# BiasTee.net
KiCad netlist of a schematic drawn in Altium Designer
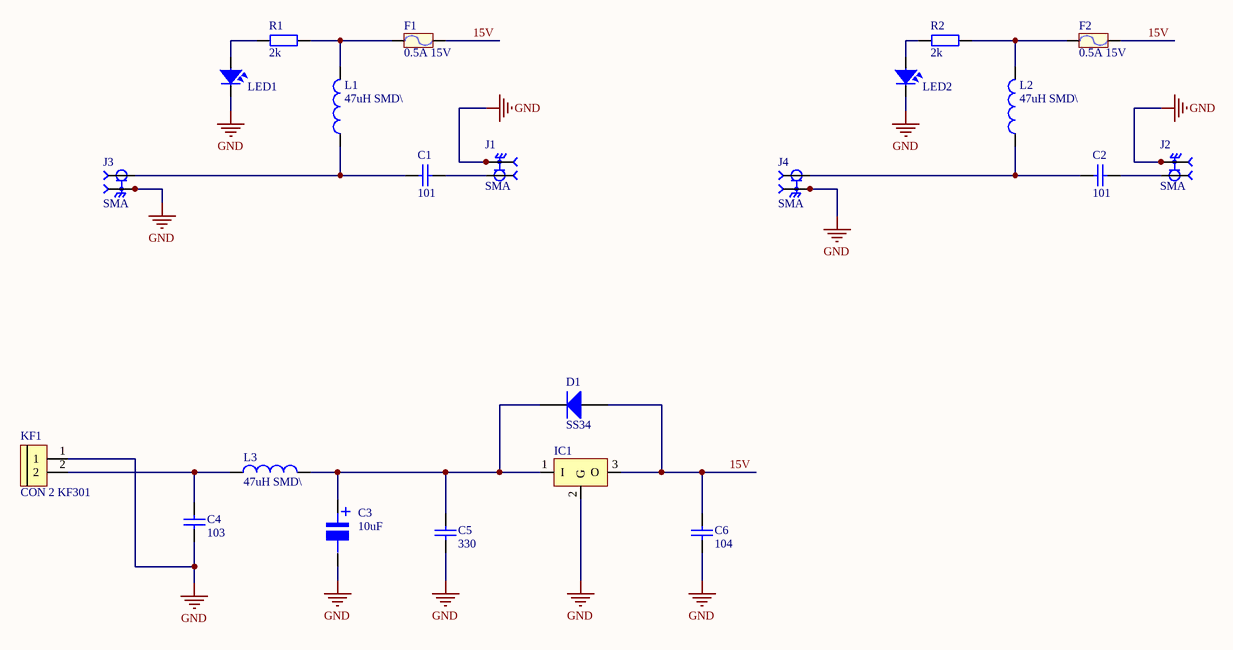
[diagram p0: BiasTee.SchDoc]

(export (version "E")
  (design (tool "Eeschema 10.0.6"))
  (components
    (comp (ref "C1")
      (value "101")
      (footprint "tu 0805")
      (description "Dán")
      (libsource (lib "Tu dien") (part "Tu 0805 101 50V 20%"))
    )
    (comp (ref "C2")
      (value "101")
      (footprint "tu 0805")
      (description "Dán")
      (libsource (lib "Tu dien") (part "Tu 0805 101 50V 20%"))
    )
    (comp (ref "C3")
      (value "10uF")
      (footprint "tu nhom 5 (c)")
      (description "Dán")
      (libsource (lib "Tu dien") (part "Tu Nhom 10uF 20V"))
    )
    (comp (ref "C4")
      (value "103")
      (footprint "tu 1206")
      (description "Dán")
      (libsource (lib "Tu dien") (part "Tu 1206 103 50V 10%"))
    )
    (comp (ref "C5")
      (value "330")
      (footprint "tu 1206")
      (description "Dán")
      (libsource (lib "Tu dien") (part "Tu 1206 103 50V 10%"))
    )
    (comp (ref "C6")
      (value "104")
      (footprint "tu 1206")
      (description "Dán")
      (libsource (lib "Tu dien") (part "Tu 1206 103 50V 10%"))
    )
    (comp (ref "D1")
      (value "SS34")
      (footprint "DIODE SMA")
      (description "Dán")
      (libsource (lib "Diode") (part "Diode SS34 ( 1N5822 )"))
    )
    (comp (ref "F1")
      (value "0.5A 15V")
      (footprint "Cau chi tu phuc hoi 2A 24V SMD1812")
      (description "2A 24V SMD1812")
      (libsource (lib "Component") (part "Cau chi tu phuc hoi 2A 24V SMD1812"))
    )
    (comp (ref "F2")
      (value "0.5A 15V")
      (footprint "Cau chi tu phuc hoi 2A 24V SMD1812")
      (description "2A 24V SMD1812")
      (libsource (lib "Component") (part "Cau chi tu phuc hoi 2A 24V SMD1812"))
    )
    (comp (ref "IC1")
      (value "LM78xx")
      (footprint "TO220H1")
      (description "Positive Voltage Regulator")
      (fields (field (name "PUBLISHER") "Altium Limited"))
      (libsource (lib "Library") (part "LM78xx"))
    )
    (comp (ref "J1")
      (value "SMA")
      (footprint "RFSOLUTIONS_CON-SMA-EDGE-S")
      (description "SMA Connector Jack, Female Socket - Board Edge, End Launch Solder")
      (fields (field (name "MF") "RF Solutions") (field (name "DIGI-KEY_PART_NUMBER") "CON-SMA-EDGE-S-ND"))
      (libsource (lib "CON-SMA-EDGE-S") (part "CON-SMA-EDGE-S"))
    )
    (comp (ref "J2")
      (value "SMA")
      (footprint "RFSOLUTIONS_CON-SMA-EDGE-S")
      (description "SMA Connector Jack, Female Socket - Board Edge, End Launch Solder")
      (fields (field (name "MF") "RF Solutions") (field (name "DIGI-KEY_PART_NUMBER") "CON-SMA-EDGE-S-ND"))
      (libsource (lib "CON-SMA-EDGE-S") (part "CON-SMA-EDGE-S"))
    )
    (comp (ref "J3")
      (value "SMA")
      (footprint "RFSOLUTIONS_CON-SMA-EDGE-S")
      (description "SMA Connector Jack, Female Socket - Board Edge, End Launch Solder")
      (fields (field (name "MF") "RF Solutions") (field (name "DIGI-KEY_PART_NUMBER") "CON-SMA-EDGE-S-ND"))
      (libsource (lib "CON-SMA-EDGE-S") (part "CON-SMA-EDGE-S"))
    )
    (comp (ref "J4")
      (value "SMA")
      (footprint "RFSOLUTIONS_CON-SMA-EDGE-S")
      (description "SMA Connector Jack, Female Socket - Board Edge, End Launch Solder")
      (fields (field (name "MF") "RF Solutions") (field (name "DIGI-KEY_PART_NUMBER") "CON-SMA-EDGE-S-ND"))
      (libsource (lib "CON-SMA-EDGE-S") (part "CON-SMA-EDGE-S"))
    )
    (comp (ref "KF1")
      (value "CON 2 KF301")
      (footprint "Con 2 KF301 5.08")
      (description "Cắm")
      (libsource (lib "Connector") (part "CON 2 KF301"))
    )
    (comp (ref "L1")
      (value "47uH SM~{D}")
      (footprint "IND_1210")
      (description "Fixed Inductors 18uH 10% 2.52MHz")
      (fields
        (field (name "MANUFACTURER") "Wurth Electronics")
        (field (name "MANUFACTURER PART NUMBER") "CMH322522-180KL")
      )
      (libsource (lib "Cuon Cam") (part "IND_18uH-0.12A-10%-SMD"))
    )
    (comp (ref "L2")
      (value "47uH SM~{D}")
      (footprint "IND_1210")
      (description "Fixed Inductors 18uH 10% 2.52MHz")
      (fields
        (field (name "MANUFACTURER") "Wurth Electronics")
        (field (name "MANUFACTURER PART NUMBER") "CMH322522-180KL")
      )
      (libsource (lib "Cuon Cam") (part "IND_18uH-0.12A-10%-SMD"))
    )
    (comp (ref "L3")
      (value "47uH SM~{D}")
      (footprint "IND_1210")
      (description "Fixed Inductors 18uH 10% 2.52MHz")
      (fields
        (field (name "MANUFACTURER") "Wurth Electronics")
        (field (name "MANUFACTURER PART NUMBER") "CMH322522-180KL")
      )
      (libsource (lib "Cuon Cam") (part "IND_18uH-0.12A-10%-SMD"))
    )
    (comp (ref "LED1")
      (value "LED")
      (footprint "LED-1206-Green")
      (libsource (lib "Library") (part "LED SMD"))
    )
    (comp (ref "LED2")
      (value "LED")
      (footprint "LED-1206-Green")
      (libsource (lib "Library") (part "LED SMD"))
    )
    (comp (ref "R1")
      (value "2k")
      (footprint "tro smd 0805")
      (description "Dán")
      (libsource (lib "Dien Tro") (part "Tro 0805 1% 2k"))
    )
    (comp (ref "R2")
      (value "2k")
      (footprint "tro smd 0805")
      (description "Dán")
      (libsource (lib "Dien Tro") (part "Tro 0805 1% 2k"))
    )
  )
  (nets
    (net (code "1") (name "/15V") (class "Default")
      (node (ref "C6") (pin "1") (pinfunction "1_1") (pintype "passive"))
      (node (ref "D1") (pin "1") (pinfunction "A_1") (pintype "passive"))
      (node (ref "F1") (pin "2") (pinfunction "2_2") (pintype "passive"))
      (node (ref "F2") (pin "2") (pinfunction "2_2") (pintype "passive"))
      (node (ref "IC1") (pin "3") (pinfunction "O_3") (pintype "power_in"))
    )
    (net (code "2") (name "GND") (class "Default")
      (node (ref "C3") (pin "2") (pinfunction "2_2") (pintype "passive"))
      (node (ref "C4") (pin "2") (pinfunction "2_2") (pintype "passive"))
      (node (ref "C5") (pin "2") (pinfunction "2_2") (pintype "passive"))
      (node (ref "C6") (pin "2") (pinfunction "2_2") (pintype "passive"))
      (node (ref "IC1") (pin "2") (pinfunction "G_2") (pintype "power_in"))
      (node (ref "J1") (pin "G1") (pinfunction "2_G1") (pintype "passive"))
      (node (ref "J1") (pin "G2") (pinfunction "2_G2") (pintype "passive"))
      (node (ref "J1") (pin "G3") (pinfunction "2_G3") (pintype "passive"))
      (node (ref "J1") (pin "G4") (pinfunction "2_G4") (pintype "passive"))
      (node (ref "J2") (pin "G1") (pinfunction "2_G1") (pintype "passive"))
      (node (ref "J2") (pin "G2") (pinfunction "2_G2") (pintype "passive"))
      (node (ref "J2") (pin "G3") (pinfunction "2_G3") (pintype "passive"))
      (node (ref "J2") (pin "G4") (pinfunction "2_G4") (pintype "passive"))
      (node (ref "J3") (pin "G1") (pinfunction "2_G1") (pintype "passive"))
      (node (ref "J3") (pin "G2") (pinfunction "2_G2") (pintype "passive"))
      (node (ref "J3") (pin "G3") (pinfunction "2_G3") (pintype "passive"))
      (node (ref "J3") (pin "G4") (pinfunction "2_G4") (pintype "passive"))
      (node (ref "J4") (pin "G1") (pinfunction "2_G1") (pintype "passive"))
      (node (ref "J4") (pin "G2") (pinfunction "2_G2") (pintype "passive"))
      (node (ref "J4") (pin "G3") (pinfunction "2_G3") (pintype "passive"))
      (node (ref "J4") (pin "G4") (pinfunction "2_G4") (pintype "passive"))
      (node (ref "KF1") (pin "1") (pinfunction "1_1") (pintype "passive"))
      (node (ref "LED1") (pin "2") (pinfunction "2_2") (pintype "passive"))
      (node (ref "LED2") (pin "2") (pinfunction "2_2") (pintype "passive"))
    )
    (net (code "3") (name "Net-(C1-Pad1)") (class "Default")
      (node (ref "C1") (pin "1") (pinfunction "1_1") (pintype "passive"))
      (node (ref "J1") (pin "1") (pinfunction "1_1") (pintype "passive"))
    )
    (net (code "4") (name "Net-(C1-Pad2)") (class "Default")
      (node (ref "C1") (pin "2") (pinfunction "2_2") (pintype "passive"))
      (node (ref "J3") (pin "1") (pinfunction "1_1") (pintype "passive"))
      (node (ref "L1") (pin "1") (pinfunction "1_1") (pintype "passive"))
    )
    (net (code "5") (name "Net-(C2-Pad1)") (class "Default")
      (node (ref "C2") (pin "1") (pinfunction "1_1") (pintype "passive"))
      (node (ref "J2") (pin "1") (pinfunction "1_1") (pintype "passive"))
    )
    (net (code "6") (name "Net-(C2-Pad2)") (class "Default")
      (node (ref "C2") (pin "2") (pinfunction "2_2") (pintype "passive"))
      (node (ref "J4") (pin "1") (pinfunction "1_1") (pintype "passive"))
      (node (ref "L2") (pin "1") (pinfunction "1_1") (pintype "passive"))
    )
    (net (code "7") (name "Net-(C4-Pad1)") (class "Default")
      (node (ref "C4") (pin "1") (pinfunction "1_1") (pintype "passive"))
      (node (ref "KF1") (pin "2") (pinfunction "2_2") (pintype "passive"))
      (node (ref "L3") (pin "1") (pinfunction "1_1") (pintype "passive"))
    )
    (net (code "8") (name "Net-(D1-K)") (class "Default")
      (node (ref "C3") (pin "1") (pinfunction "1_1") (pintype "passive"))
      (node (ref "C5") (pin "1") (pinfunction "1_1") (pintype "passive"))
      (node (ref "D1") (pin "2") (pinfunction "K_2") (pintype "passive"))
      (node (ref "IC1") (pin "1") (pinfunction "I_1") (pintype "power_in"))
      (node (ref "L3") (pin "2") (pinfunction "2_2") (pintype "passive"))
    )
    (net (code "9") (name "Net-(F1-Pad1)") (class "Default")
      (node (ref "F1") (pin "1") (pinfunction "1_1") (pintype "passive"))
      (node (ref "L1") (pin "2") (pinfunction "2_2") (pintype "passive"))
      (node (ref "R1") (pin "2") (pinfunction "2_2") (pintype "passive"))
    )
    (net (code "10") (name "Net-(F2-Pad1)") (class "Default")
      (node (ref "F2") (pin "1") (pinfunction "1_1") (pintype "passive"))
      (node (ref "L2") (pin "2") (pinfunction "2_2") (pintype "passive"))
      (node (ref "R2") (pin "2") (pinfunction "2_2") (pintype "passive"))
    )
    (net (code "11") (name "Net-(LED1-Pad1)") (class "Default")
      (node (ref "LED1") (pin "1") (pinfunction "1_1") (pintype "passive"))
      (node (ref "R1") (pin "1") (pinfunction "1_1") (pintype "passive"))
    )
    (net (code "12") (name "Net-(LED2-Pad1)") (class "Default")
      (node (ref "LED2") (pin "1") (pinfunction "1_1") (pintype "passive"))
      (node (ref "R2") (pin "1") (pinfunction "1_1") (pintype "passive"))
    )
  )
)
